# Serial.net
KiCad netlist of a schematic drawn in Altium Designer
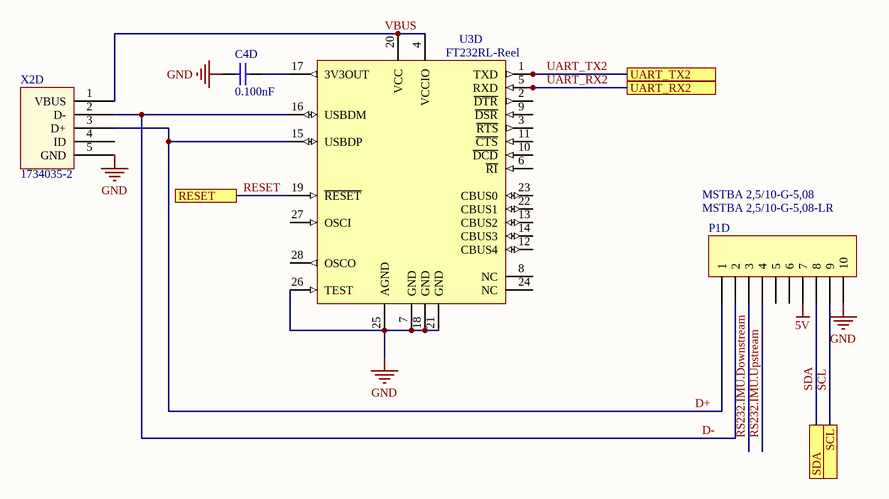
[diagram p0: Serial.SchDoc]

(export (version "E")
  (design (tool "Eeschema 10.0.6"))
  (components
    (comp (ref "C4D")
      (value "0.100nF")
      (footprint "C0805")
      (description "Unpolarized Capacitor")
      (fields (field (name "Comment") "Cap"))
      (libsource (lib "URC_Lib") (part "Cap"))
    )
    (comp (ref "P1D")
      (value "MSTBA 2,5/10-G-5,08")
      (footprint "MSTBA 2,5/10-G-5,08")
      (description "Header, 10-Pin")
      (fields (field (name "MANUFACTURER PART NUMBER") "MSTBA 2,5/10-G-5,08-LR"))
      (libsource (lib "Pheonix Contact") (part "MSTBA 2,5/10-G-5,08"))
    )
    (comp (ref "U3D")
      (value "FT232RL-Reel")
      (footprint "SSOP-28_N")
      (description "USB UART Asynchronous Serial Data Transfer Chip, 28-pin SSOP, Tape and Reel")
      (fields (field (name "MANUFACTURER") "FTDI"))
      (libsource (lib "FTDI FT Series") (part "FT232RL-Reel"))
    )
    (comp (ref "X2D")
      (value "USB Mini Jack")
      (footprint "UX60-MB-5ST")
      (description "USB Mini connector")
      (fields (field (name "MANUFACTURER PART NUMBER") "1734035-2"))
      (libsource (lib "URC") (part "USB-MINI"))
    )
  )
  (nets
    (net (code "1") (name "/D+") (class "Default")
      (node (ref "P1D") (pin "1") (pinfunction "1_1") (pintype "passive"))
      (node (ref "U3D") (pin "15") (pinfunction "USBDP_15") (pintype "bidirectional"))
      (node (ref "X2D") (pin "3") (pinfunction "D+_3") (pintype "passive"))
    )
    (net (code "2") (name "/D-") (class "Default")
      (node (ref "P1D") (pin "2") (pinfunction "2_2") (pintype "passive"))
      (node (ref "U3D") (pin "16") (pinfunction "USBDM_16") (pintype "bidirectional"))
      (node (ref "X2D") (pin "2") (pinfunction "D-_2") (pintype "passive"))
    )
    (net (code "3") (name "/RESET") (class "Default")
      (node (ref "U3D") (pin "19") (pinfunction "~{RESET}_19") (pintype "input"))
    )
    (net (code "4") (name "/RS232.IMU.Downstream") (class "Default")
      (node (ref "P1D") (pin "3") (pinfunction "3_3") (pintype "passive"))
    )
    (net (code "5") (name "/RS232.IMU.Upstream") (class "Default")
      (node (ref "P1D") (pin "4") (pinfunction "4_4") (pintype "passive"))
    )
    (net (code "6") (name "/SCL") (class "Default")
      (node (ref "P1D") (pin "9") (pinfunction "9_9") (pintype "passive"))
    )
    (net (code "7") (name "/SDA") (class "Default")
      (node (ref "P1D") (pin "8") (pinfunction "8_8") (pintype "passive"))
    )
    (net (code "8") (name "/UART_RX2") (class "Default")
      (node (ref "U3D") (pin "5") (pinfunction "RXD_5") (pintype "input"))
    )
    (net (code "9") (name "/UART_TX2") (class "Default")
      (node (ref "U3D") (pin "1") (pinfunction "TXD_1") (pintype "output"))
    )
    (net (code "10") (name "/VBUS") (class "Default")
      (node (ref "U3D") (pin "20") (pinfunction "VCC_20") (pintype "power_in"))
      (node (ref "U3D") (pin "4") (pinfunction "VCCIO_4") (pintype "power_in"))
      (node (ref "X2D") (pin "1") (pinfunction "VBUS_1") (pintype "passive"))
    )
    (net (code "11") (name "5V") (class "Default")
      (node (ref "P1D") (pin "7") (pinfunction "7_7") (pintype "passive"))
    )
    (net (code "12") (name "GND") (class "Default")
      (node (ref "C4D") (pin "2") (pinfunction "2_2") (pintype "passive"))
      (node (ref "P1D") (pin "10") (pinfunction "10_10") (pintype "passive"))
      (node (ref "U3D") (pin "18") (pinfunction "GND_18") (pintype "power_in"))
      (node (ref "U3D") (pin "21") (pinfunction "GND_21") (pintype "power_in"))
      (node (ref "U3D") (pin "25") (pinfunction "AGND_25") (pintype "power_in"))
      (node (ref "U3D") (pin "26") (pinfunction "TEST_26") (pintype "input"))
      (node (ref "U3D") (pin "7") (pinfunction "GND_7") (pintype "power_in"))
      (node (ref "X2D") (pin "5") (pinfunction "GND_5") (pintype "passive"))
    )
    (net (code "13") (name "Net-(U3D-3V3OUT)") (class "Default")
      (node (ref "C4D") (pin "1") (pinfunction "1_1") (pintype "passive"))
      (node (ref "U3D") (pin "17") (pinfunction "3V3OUT_17") (pintype "output"))
    )
    (net (code "14") (name "unconnected-(P1D-Pad5)") (class "Default")
      (node (ref "P1D") (pin "5") (pinfunction "5_5") (pintype "passive"))
    )
    (net (code "15") (name "unconnected-(P1D-Pad6)") (class "Default")
      (node (ref "P1D") (pin "6") (pinfunction "6_6") (pintype "passive"))
    )
    (net (code "16") (name "unconnected-(U3D-CBUS0-Pad23)") (class "Default")
      (node (ref "U3D") (pin "23") (pinfunction "CBUS0_23") (pintype "bidirectional"))
    )
    (net (code "17") (name "unconnected-(U3D-CBUS1-Pad22)") (class "Default")
      (node (ref "U3D") (pin "22") (pinfunction "CBUS1_22") (pintype "bidirectional"))
    )
    (net (code "18") (name "unconnected-(U3D-CBUS2-Pad13)") (class "Default")
      (node (ref "U3D") (pin "13") (pinfunction "CBUS2_13") (pintype "bidirectional"))
    )
    (net (code "19") (name "unconnected-(U3D-CBUS3-Pad14)") (class "Default")
      (node (ref "U3D") (pin "14") (pinfunction "CBUS3_14") (pintype "bidirectional"))
    )
    (net (code "20") (name "unconnected-(U3D-CBUS4-Pad12)") (class "Default")
      (node (ref "U3D") (pin "12") (pinfunction "CBUS4_12") (pintype "bidirectional"))
    )
    (net (code "21") (name "unconnected-(U3D-NC-Pad8)") (class "Default")
      (node (ref "U3D") (pin "8") (pinfunction "NC_8") (pintype "passive"))
    )
    (net (code "22") (name "unconnected-(U3D-NC-Pad24)") (class "Default")
      (node (ref "U3D") (pin "24") (pinfunction "NC_24") (pintype "passive"))
    )
    (net (code "23") (name "unconnected-(U3D-OSCI-Pad27)") (class "Default")
      (node (ref "U3D") (pin "27") (pinfunction "OSCI_27") (pintype "input"))
    )
    (net (code "24") (name "unconnected-(U3D-OSCO-Pad28)") (class "Default")
      (node (ref "U3D") (pin "28") (pinfunction "OSCO_28") (pintype "output"))
    )
    (net (code "25") (name "unconnected-(U3D-~{CTS}-Pad11)") (class "Default")
      (node (ref "U3D") (pin "11") (pinfunction "~{CTS}_11") (pintype "input"))
    )
    (net (code "26") (name "unconnected-(U3D-~{DCD}-Pad10)") (class "Default")
      (node (ref "U3D") (pin "10") (pinfunction "~{DCD}_10") (pintype "input"))
    )
    (net (code "27") (name "unconnected-(U3D-~{DSR}-Pad9)") (class "Default")
      (node (ref "U3D") (pin "9") (pinfunction "~{DSR}_9") (pintype "input"))
    )
    (net (code "28") (name "unconnected-(U3D-~{DTR}-Pad2)") (class "Default")
      (node (ref "U3D") (pin "2") (pinfunction "~{DTR}_2") (pintype "output"))
    )
    (net (code "29") (name "unconnected-(U3D-~{RI}-Pad6)") (class "Default")
      (node (ref "U3D") (pin "6") (pinfunction "~{RI}_6") (pintype "input"))
    )
    (net (code "30") (name "unconnected-(U3D-~{RTS}-Pad3)") (class "Default")
      (node (ref "U3D") (pin "3") (pinfunction "~{RTS}_3") (pintype "output"))
    )
    (net (code "31") (name "unconnected-(X2D-ID-Pad4)") (class "Default")
      (node (ref "X2D") (pin "4") (pinfunction "ID_4") (pintype "passive"))
    )
  )
)
